# ProPrj_USBC_Hub_2025-04-12.net
KiCad netlist of a schematic drawn in EasyEDA Pro
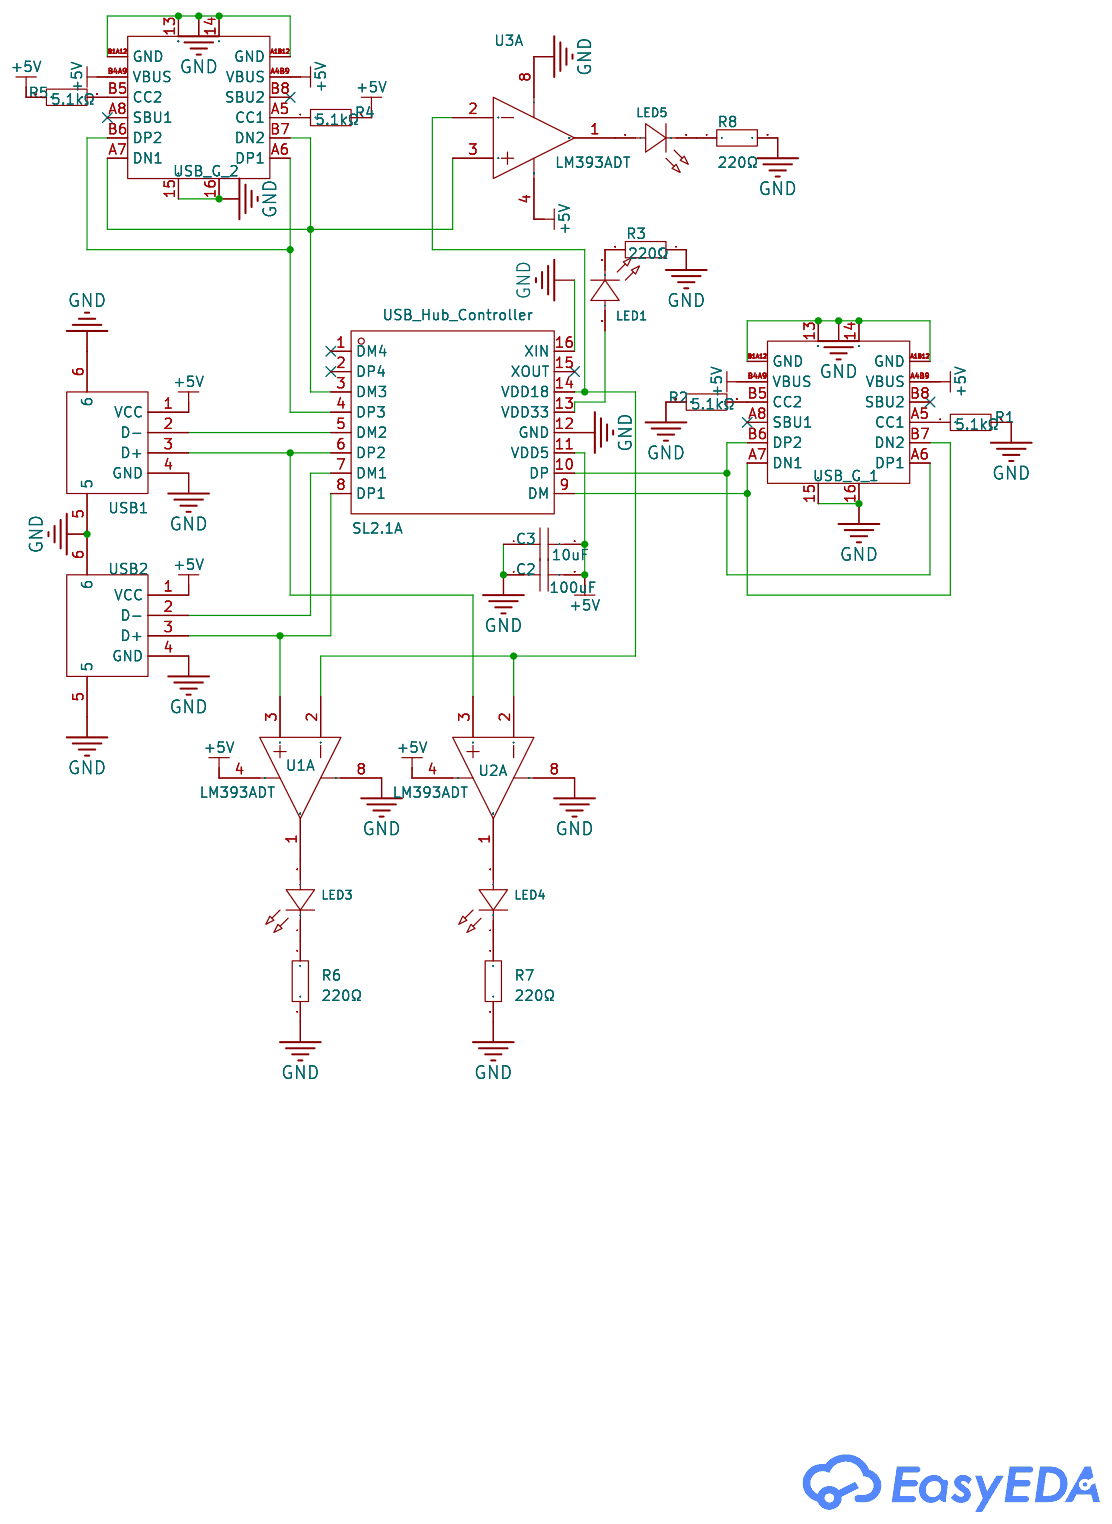
[diagram p0: schematic sheet]

(export (version "E")
  (design (tool "Eeschema 10.0.6"))
  (components
    (comp (ref "C2")
      (value "100uF")
      (footprint "easyedapro:C0603")
      (fields
        (field (name "Manufacturer Part") "CL31A107MQHNNNE")
        (field (name "Manufacturer") "SAMSUNG(三星)")
      )
      (libsource (lib "easyedapro") (part "CL10A106KP8NNNC"))
    )
    (comp (ref "C3")
      (value "10uF")
      (footprint "easyedapro:C0603")
      (fields
        (field (name "Manufacturer Part") "CL10A106KP8NNNC")
        (field (name "Manufacturer") "SAMSUNG(三星)")
      )
      (libsource (lib "easyedapro") (part "CL10A106KP8NNNC"))
    )
    (comp (ref "LED1")
      (value "XL-1608UWC-04")
      (footprint "easyedapro:LED0603-RD_WHITE")
      (fields (field (name "Manufacturer") "XINGLIGHT(成兴光)"))
      (libsource (lib "easyedapro") (part "XL-1608UWC-04"))
    )
    (comp (ref "LED3")
      (value "XL-1608UWC-04")
      (footprint "easyedapro:LED0603-RD_WHITE")
      (fields (field (name "Manufacturer") "XINGLIGHT(成兴光)"))
      (libsource (lib "easyedapro") (part "XL-1608UWC-04"))
    )
    (comp (ref "LED4")
      (value "XL-1608UWC-04")
      (footprint "easyedapro:LED0603-RD_WHITE")
      (fields (field (name "Manufacturer") "XINGLIGHT(成兴光)"))
      (libsource (lib "easyedapro") (part "XL-1608UWC-04"))
    )
    (comp (ref "LED5")
      (value "XL-1608UWC-04")
      (footprint "easyedapro:LED0603-RD_WHITE")
      (fields (field (name "Manufacturer") "XINGLIGHT(成兴光)"))
      (libsource (lib "easyedapro") (part "XL-1608UWC-04"))
    )
    (comp (ref "R1")
      (value "5.1kΩ")
      (footprint "easyedapro:R0603")
      (fields
        (field (name "Manufacturer Part") "HoAR0603-1/10W-5.1KR-0.1%-TCR25")
        (field (name "Manufacturer") "Milliohm(毫欧)")
      )
      (libsource (lib "easyedapro") (part "Res"))
    )
    (comp (ref "R2")
      (value "5.1kΩ")
      (footprint "easyedapro:R0603")
      (fields
        (field (name "Manufacturer Part") "HoAR0603-1/10W-5.1KR-0.1%-TCR25")
        (field (name "Manufacturer") "Milliohm(毫欧)")
      )
      (libsource (lib "easyedapro") (part "Res"))
    )
    (comp (ref "R3")
      (value "220Ω")
      (footprint "easyedapro:R0603")
      (fields (field (name "Manufacturer Part") "SCR0603J220R") (field (name "Manufacturer") "VO(翔胜)"))
      (libsource (lib "easyedapro") (part "Res"))
    )
    (comp (ref "R4")
      (value "5.1kΩ")
      (footprint "easyedapro:R0603")
      (fields
        (field (name "Manufacturer Part") "HoAR0603-1/10W-5.1KR-0.1%-TCR25")
        (field (name "Manufacturer") "Milliohm(毫欧)")
      )
      (libsource (lib "easyedapro") (part "Res"))
    )
    (comp (ref "R5")
      (value "5.1kΩ")
      (footprint "easyedapro:R0603")
      (fields
        (field (name "Manufacturer Part") "HoAR0603-1/10W-5.1KR-0.1%-TCR25")
        (field (name "Manufacturer") "Milliohm(毫欧)")
      )
      (libsource (lib "easyedapro") (part "Res"))
    )
    (comp (ref "R6")
      (value "220Ω")
      (footprint "easyedapro:R0603")
      (fields (field (name "Manufacturer Part") "SCR0603J220R") (field (name "Manufacturer") "VO(翔胜)"))
      (libsource (lib "easyedapro") (part "Res"))
    )
    (comp (ref "R7")
      (value "220Ω")
      (footprint "easyedapro:R0603")
      (fields (field (name "Manufacturer Part") "SCR0603J220R") (field (name "Manufacturer") "VO(翔胜)"))
      (libsource (lib "easyedapro") (part "Res"))
    )
    (comp (ref "R8")
      (value "220Ω")
      (footprint "easyedapro:R0603")
      (fields (field (name "Manufacturer Part") "SCR0603J220R") (field (name "Manufacturer") "VO(翔胜)"))
      (libsource (lib "easyedapro") (part "Res"))
    )
    (comp (ref "U1")
      (value "LM393ADT")
      (footprint "easyedapro:SOIC-8_L4.9-W3.9-P1.27-LS6.0-BL")
      (fields (field (name "Manufacturer") "ST(意法半导体)"))
      (libsource (lib "easyedapro") (part "LM393ADT"))
    )
    (comp (ref "U2")
      (value "LM393ADT")
      (footprint "easyedapro:SOIC-8_L4.9-W3.9-P1.27-LS6.0-BL")
      (fields (field (name "Manufacturer") "ST(意法半导体)"))
      (libsource (lib "easyedapro") (part "LM393ADT"))
    )
    (comp (ref "U3")
      (value "LM393ADT")
      (footprint "easyedapro:SOIC-8_L4.9-W3.9-P1.27-LS6.0-BL")
      (fields (field (name "Manufacturer") "ST(意法半导体)"))
      (libsource (lib "easyedapro") (part "LM393ADT"))
    )
    (comp (ref "USB1")
      (value "903-131A1011D10100")
      (footprint "easyedapro:USB-A-TH_U-G-04WD-W-01")
      (fields (field (name "Manufacturer") "精拓金"))
      (libsource (lib "easyedapro") (part "U-G-04DD-W-01"))
    )
    (comp (ref "USB2")
      (value "903-131A1011D10100")
      (footprint "easyedapro:USB-A-TH_U-G-04WD-W-01")
      (fields (field (name "Manufacturer") "精拓金"))
      (libsource (lib "easyedapro") (part "U-G-04DD-W-01"))
    )
    (comp (ref "USB_C_1")
      (value "HYCW412-USBC16-065B")
      (footprint "easyedapro:USB-C-SMD_HYCW412-USBC16-065B")
      (description "Connector Type:Type-C Gender:Female Number of Contacts:16P")
      (fields (field (name "Manufacturer") "华宇创"))
      (libsource (lib "easyedapro") (part "HYCW412-USBC16-065B"))
    )
    (comp (ref "USB_C_2")
      (value "HYCW412-USBC16-065B")
      (footprint "easyedapro:USB-C-SMD_HYCW412-USBC16-065B")
      (description "Connector Type:Type-C Gender:Female Number of Contacts:16P")
      (fields (field (name "Manufacturer") "华宇创"))
      (libsource (lib "easyedapro") (part "HYCW412-USBC16-065B"))
    )
    (comp (ref "USB_Hub_Controller")
      (value "SL2.1A")
      (footprint "easyedapro:SOP-16_L10.0-W3.9-P1.27-LS6.0-BL")
      (fields (field (name "Manufacturer") "CoreChips(和芯润德)"))
      (libsource (lib "easyedapro") (part "SL2.1A"))
    )
  )
  (nets
    (net (code "1") (name "+5V") (class "Default")
      (node (ref "C2") (pin "2") (pinfunction "2_2") (pintype "unspecified"))
      (node (ref "C3") (pin "2") (pinfunction "2_2") (pintype "unspecified"))
      (node (ref "R4") (pin "2") (pinfunction "2_2") (pintype "input"))
      (node (ref "R5") (pin "1") (pinfunction "1_1") (pintype "input"))
      (node (ref "U1") (pin "4") (pinfunction "GND_4") (pintype "unspecified"))
      (node (ref "U2") (pin "4") (pinfunction "GND_4") (pintype "unspecified"))
      (node (ref "U3") (pin "4") (pinfunction "GND_4") (pintype "unspecified"))
      (node (ref "USB1") (pin "1") (pinfunction "VCC_1") (pintype "unspecified"))
      (node (ref "USB2") (pin "1") (pinfunction "VCC_1") (pintype "unspecified"))
      (node (ref "USB_C_1") (pin "A4B9") (pinfunction "VBUS_A4B9") (pintype "unspecified"))
      (node (ref "USB_C_1") (pin "B4A9") (pinfunction "VBUS_B4A9") (pintype "unspecified"))
      (node (ref "USB_C_2") (pin "A4B9") (pinfunction "VBUS_A4B9") (pintype "unspecified"))
      (node (ref "USB_C_2") (pin "B4A9") (pinfunction "VBUS_B4A9") (pintype "unspecified"))
      (node (ref "USB_Hub_Controller") (pin "11") (pinfunction "VDD5_11") (pintype "unspecified"))
    )
    (net (code "2") (name "GND") (class "Default")
      (node (ref "C2") (pin "1") (pinfunction "1_1") (pintype "unspecified"))
      (node (ref "C3") (pin "1") (pinfunction "1_1") (pintype "unspecified"))
      (node (ref "R1") (pin "2") (pinfunction "2_2") (pintype "input"))
      (node (ref "R2") (pin "1") (pinfunction "1_1") (pintype "input"))
      (node (ref "R3") (pin "1") (pinfunction "1_1") (pintype "input"))
      (node (ref "R6") (pin "2") (pinfunction "2_2") (pintype "input"))
      (node (ref "R7") (pin "2") (pinfunction "2_2") (pintype "input"))
      (node (ref "R8") (pin "2") (pinfunction "2_2") (pintype "input"))
      (node (ref "U1") (pin "8") (pinfunction "V+_8") (pintype "unspecified"))
      (node (ref "U2") (pin "8") (pinfunction "V+_8") (pintype "unspecified"))
      (node (ref "U3") (pin "8") (pinfunction "V+_8") (pintype "unspecified"))
      (node (ref "USB1") (pin "4") (pinfunction "GND_4") (pintype "unspecified"))
      (node (ref "USB1") (pin "5") (pinfunction "5_5") (pintype "unspecified"))
      (node (ref "USB1") (pin "6") (pinfunction "6_6") (pintype "unspecified"))
      (node (ref "USB2") (pin "4") (pinfunction "GND_4") (pintype "unspecified"))
      (node (ref "USB2") (pin "5") (pinfunction "5_5") (pintype "unspecified"))
      (node (ref "USB2") (pin "6") (pinfunction "6_6") (pintype "unspecified"))
      (node (ref "USB_C_1") (pin "13") (pinfunction "13_13") (pintype "unspecified"))
      (node (ref "USB_C_1") (pin "14") (pinfunction "14_14") (pintype "unspecified"))
      (node (ref "USB_C_1") (pin "15") (pinfunction "15_15") (pintype "unspecified"))
      (node (ref "USB_C_1") (pin "16") (pinfunction "16_16") (pintype "unspecified"))
      (node (ref "USB_C_1") (pin "A1B12") (pinfunction "GND_A1B12") (pintype "unspecified"))
      (node (ref "USB_C_1") (pin "B1A12") (pinfunction "GND_B1A12") (pintype "unspecified"))
      (node (ref "USB_C_2") (pin "13") (pinfunction "13_13") (pintype "unspecified"))
      (node (ref "USB_C_2") (pin "14") (pinfunction "14_14") (pintype "unspecified"))
      (node (ref "USB_C_2") (pin "15") (pinfunction "15_15") (pintype "unspecified"))
      (node (ref "USB_C_2") (pin "16") (pinfunction "16_16") (pintype "unspecified"))
      (node (ref "USB_C_2") (pin "A1B12") (pinfunction "GND_A1B12") (pintype "unspecified"))
      (node (ref "USB_C_2") (pin "B1A12") (pinfunction "GND_B1A12") (pintype "unspecified"))
      (node (ref "USB_Hub_Controller") (pin "12") (pinfunction "GND_12") (pintype "unspecified"))
      (node (ref "USB_Hub_Controller") (pin "16") (pinfunction "XIN_16") (pintype "unspecified"))
    )
    (net (code "3") (name "Net-(LED1-A)") (class "Default")
      (node (ref "LED1") (pin "2") (pinfunction "A_2") (pintype "input"))
      (node (ref "USB_Hub_Controller") (pin "13") (pinfunction "VDD33_13") (pintype "unspecified"))
    )
    (net (code "4") (name "Net-(LED1-K)") (class "Default")
      (node (ref "LED1") (pin "1") (pinfunction "K_1") (pintype "input"))
      (node (ref "R3") (pin "2") (pinfunction "2_2") (pintype "input"))
    )
    (net (code "5") (name "Net-(LED3-A)") (class "Default")
      (node (ref "LED3") (pin "2") (pinfunction "A_2") (pintype "input"))
      (node (ref "U1") (pin "1") (pinfunction "OUT_1") (pintype "output"))
    )
    (net (code "6") (name "Net-(LED3-K)") (class "Default")
      (node (ref "LED3") (pin "1") (pinfunction "K_1") (pintype "input"))
      (node (ref "R6") (pin "1") (pinfunction "1_1") (pintype "input"))
    )
    (net (code "7") (name "Net-(LED4-A)") (class "Default")
      (node (ref "LED4") (pin "2") (pinfunction "A_2") (pintype "input"))
      (node (ref "U2") (pin "1") (pinfunction "OUT_1") (pintype "output"))
    )
    (net (code "8") (name "Net-(LED4-K)") (class "Default")
      (node (ref "LED4") (pin "1") (pinfunction "K_1") (pintype "input"))
      (node (ref "R7") (pin "1") (pinfunction "1_1") (pintype "input"))
    )
    (net (code "9") (name "Net-(LED5-A)") (class "Default")
      (node (ref "LED5") (pin "2") (pinfunction "A_2") (pintype "input"))
      (node (ref "U3") (pin "1") (pinfunction "OUT_1") (pintype "output"))
    )
    (net (code "10") (name "Net-(LED5-K)") (class "Default")
      (node (ref "LED5") (pin "1") (pinfunction "K_1") (pintype "input"))
      (node (ref "R8") (pin "1") (pinfunction "1_1") (pintype "input"))
    )
    (net (code "11") (name "Net-(U1A-IN+)") (class "Default")
      (node (ref "U1") (pin "3") (pinfunction "IN+_3") (pintype "unspecified"))
      (node (ref "USB2") (pin "3") (pinfunction "D+_3") (pintype "unspecified"))
      (node (ref "USB_Hub_Controller") (pin "8") (pinfunction "DP1_8") (pintype "unspecified"))
    )
    (net (code "12") (name "Net-(U1A-IN-)") (class "Default")
      (node (ref "U1") (pin "2") (pinfunction "IN-_2") (pintype "unspecified"))
      (node (ref "U2") (pin "2") (pinfunction "IN-_2") (pintype "unspecified"))
      (node (ref "U3") (pin "2") (pinfunction "IN-_2") (pintype "unspecified"))
      (node (ref "USB_Hub_Controller") (pin "14") (pinfunction "VDD18_14") (pintype "unspecified"))
    )
    (net (code "13") (name "Net-(U2A-IN+)") (class "Default")
      (node (ref "U2") (pin "3") (pinfunction "IN+_3") (pintype "unspecified"))
      (node (ref "USB1") (pin "3") (pinfunction "D+_3") (pintype "unspecified"))
      (node (ref "USB_Hub_Controller") (pin "6") (pinfunction "DP2_6") (pintype "unspecified"))
    )
    (net (code "14") (name "Net-(U3A-IN+)") (class "Default")
      (node (ref "U3") (pin "3") (pinfunction "IN+_3") (pintype "unspecified"))
      (node (ref "USB_C_2") (pin "A7") (pinfunction "DN1_A7") (pintype "unspecified"))
      (node (ref "USB_C_2") (pin "B7") (pinfunction "DN2_B7") (pintype "unspecified"))
      (node (ref "USB_Hub_Controller") (pin "3") (pinfunction "DM3_3") (pintype "unspecified"))
    )
    (net (code "15") (name "Net-(USB1-D-)") (class "Default")
      (node (ref "USB1") (pin "2") (pinfunction "D-_2") (pintype "unspecified"))
      (node (ref "USB_Hub_Controller") (pin "5") (pinfunction "DM2_5") (pintype "unspecified"))
    )
    (net (code "16") (name "Net-(USB2-D-)") (class "Default")
      (node (ref "USB2") (pin "2") (pinfunction "D-_2") (pintype "unspecified"))
      (node (ref "USB_Hub_Controller") (pin "7") (pinfunction "DM1_7") (pintype "unspecified"))
    )
    (net (code "17") (name "Net-(USB_C_1-CC1)") (class "Default")
      (node (ref "R1") (pin "1") (pinfunction "1_1") (pintype "input"))
      (node (ref "USB_C_1") (pin "A5") (pinfunction "CC1_A5") (pintype "unspecified"))
    )
    (net (code "18") (name "Net-(USB_C_1-CC2)") (class "Default")
      (node (ref "R2") (pin "2") (pinfunction "2_2") (pintype "input"))
      (node (ref "USB_C_1") (pin "B5") (pinfunction "CC2_B5") (pintype "unspecified"))
    )
    (net (code "19") (name "Net-(USB_C_1-DN1)") (class "Default")
      (node (ref "USB_C_1") (pin "A7") (pinfunction "DN1_A7") (pintype "unspecified"))
      (node (ref "USB_C_1") (pin "B7") (pinfunction "DN2_B7") (pintype "unspecified"))
      (node (ref "USB_Hub_Controller") (pin "9") (pinfunction "DM_9") (pintype "unspecified"))
    )
    (net (code "20") (name "Net-(USB_C_1-DP1)") (class "Default")
      (node (ref "USB_C_1") (pin "A6") (pinfunction "DP1_A6") (pintype "unspecified"))
      (node (ref "USB_C_1") (pin "B6") (pinfunction "DP2_B6") (pintype "unspecified"))
      (node (ref "USB_Hub_Controller") (pin "10") (pinfunction "DP_10") (pintype "unspecified"))
    )
    (net (code "21") (name "Net-(USB_C_2-CC1)") (class "Default")
      (node (ref "R4") (pin "1") (pinfunction "1_1") (pintype "input"))
      (node (ref "USB_C_2") (pin "A5") (pinfunction "CC1_A5") (pintype "unspecified"))
    )
    (net (code "22") (name "Net-(USB_C_2-CC2)") (class "Default")
      (node (ref "R5") (pin "2") (pinfunction "2_2") (pintype "input"))
      (node (ref "USB_C_2") (pin "B5") (pinfunction "CC2_B5") (pintype "unspecified"))
    )
    (net (code "23") (name "Net-(USB_C_2-DP1)") (class "Default")
      (node (ref "USB_C_2") (pin "A6") (pinfunction "DP1_A6") (pintype "unspecified"))
      (node (ref "USB_C_2") (pin "B6") (pinfunction "DP2_B6") (pintype "unspecified"))
      (node (ref "USB_Hub_Controller") (pin "4") (pinfunction "DP3_4") (pintype "unspecified"))
    )
    (net (code "24") (name "unconnected-(USB_C_1-SBU1-PadA8)") (class "Default")
      (node (ref "USB_C_1") (pin "A8") (pinfunction "SBU1_A8") (pintype "unspecified+no_connect"))
    )
    (net (code "25") (name "unconnected-(USB_C_1-SBU2-PadB8)") (class "Default")
      (node (ref "USB_C_1") (pin "B8") (pinfunction "SBU2_B8") (pintype "unspecified+no_connect"))
    )
    (net (code "26") (name "unconnected-(USB_C_2-SBU1-PadA8)") (class "Default")
      (node (ref "USB_C_2") (pin "A8") (pinfunction "SBU1_A8") (pintype "unspecified+no_connect"))
    )
    (net (code "27") (name "unconnected-(USB_C_2-SBU2-PadB8)") (class "Default")
      (node (ref "USB_C_2") (pin "B8") (pinfunction "SBU2_B8") (pintype "unspecified+no_connect"))
    )
    (net (code "28") (name "unconnected-(USB_Hub_Controller-DM4-Pad1)") (class "Default")
      (node (ref "USB_Hub_Controller") (pin "1") (pinfunction "DM4_1") (pintype "unspecified+no_connect"))
    )
    (net (code "29") (name "unconnected-(USB_Hub_Controller-DP4-Pad2)") (class "Default")
      (node (ref "USB_Hub_Controller") (pin "2") (pinfunction "DP4_2") (pintype "unspecified+no_connect"))
    )
    (net (code "30") (name "unconnected-(USB_Hub_Controller-XOUT-Pad15)") (class "Default")
      (node (ref "USB_Hub_Controller") (pin "15") (pinfunction "XOUT_15") (pintype "unspecified+no_connect"))
    )
  )
)
